# SmartCar_Arduino_V4.net
KiCad netlist of a schematic drawn in EAGLE
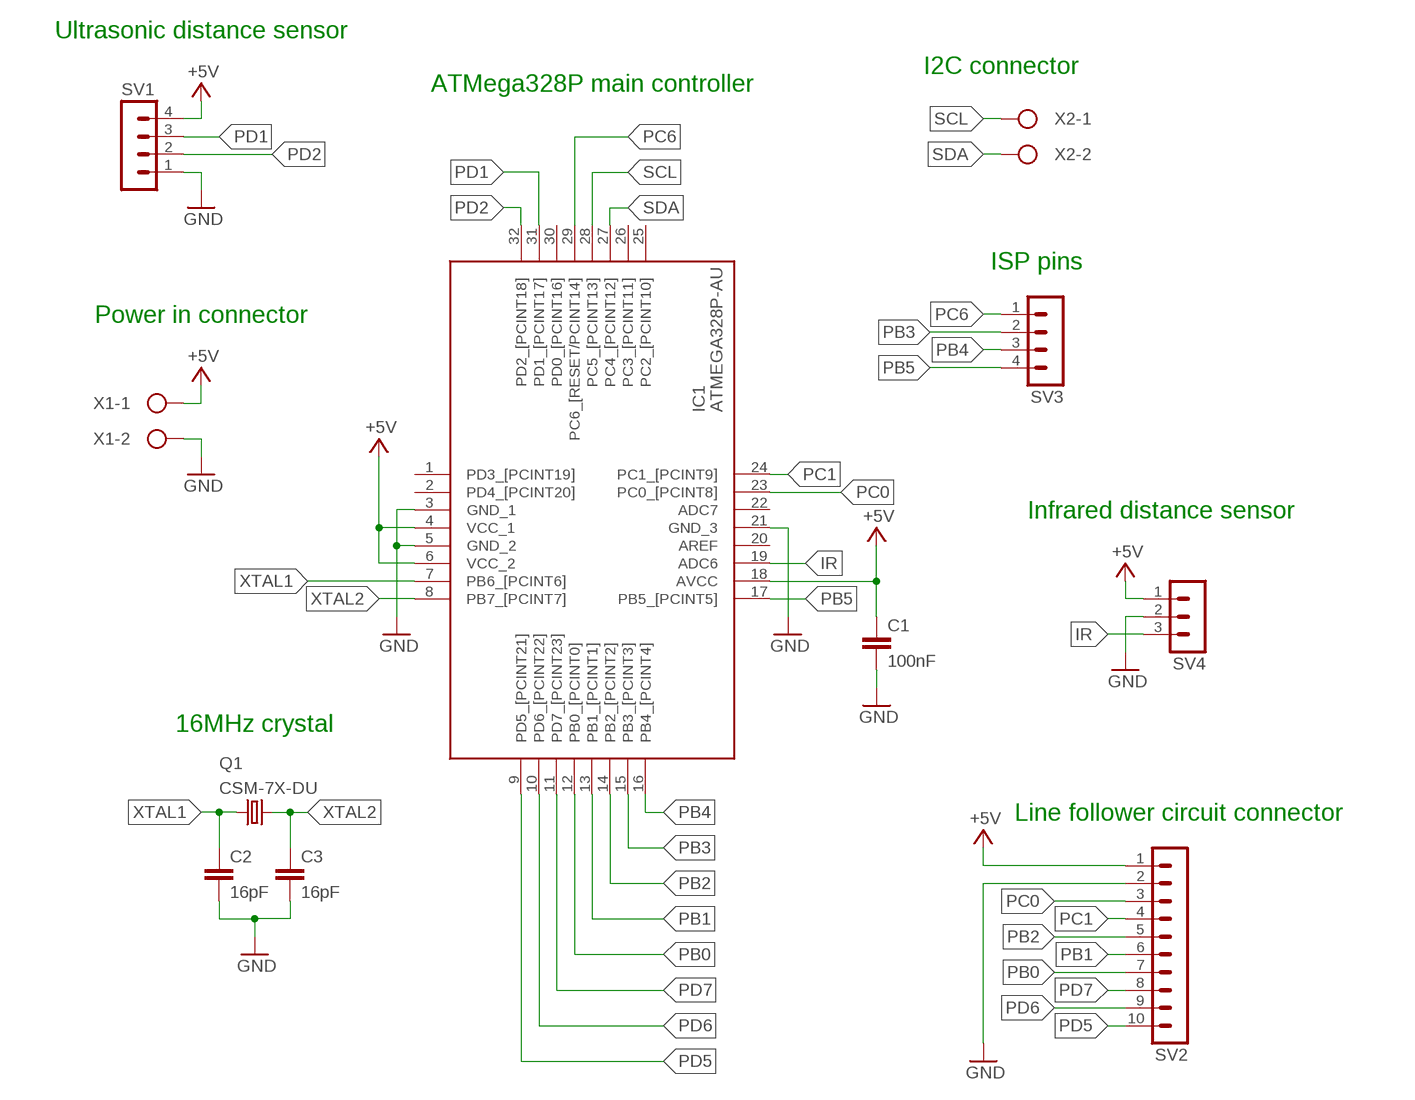
[diagram p0: schematic, sheet 1]

(export (version "E")
  (design (tool "Eeschema 10.0.6"))
  (components
    (comp (ref "C1")
      (value "100nF")
      (footprint "eagle-import:C0805")
      (libsource (lib "eagle-import") (part "C-EUC0805"))
    )
    (comp (ref "C2")
      (value "16pF")
      (footprint "eagle-import:C0805")
      (libsource (lib "eagle-import") (part "C-EUC0805"))
    )
    (comp (ref "C3")
      (value "16pF")
      (footprint "eagle-import:C0805")
      (libsource (lib "eagle-import") (part "C-EUC0805"))
    )
    (comp (ref "IC1")
      (value "ATMEGA328P-AU")
      (footprint "eagle-import:QFP80P900X900X120-32N")
      (fields (field (name "MOUSER_PART_NUMBER") "556-ATMEGA328P-AU"))
      (libsource (lib "eagle-import") (part "ATMEGA328P-AU"))
    )
    (comp (ref "Q1")
      (value "CSM-7X-DU")
      (footprint "eagle-import:CSM-7X-DU")
      (libsource (lib "eagle-import") (part "CSM-7X-DU"))
    )
    (comp (ref "SV1")
      (value "0")
      (footprint "eagle-import:MA04-1")
      (libsource (lib "eagle-import") (part "MA04-1"))
    )
    (comp (ref "SV2")
      (value "0")
      (footprint "eagle-import:MA10-1")
      (libsource (lib "eagle-import") (part "MA10-1"))
    )
    (comp (ref "SV3")
      (value "0")
      (footprint "eagle-import:MA04-1")
      (libsource (lib "eagle-import") (part "MA04-1"))
    )
    (comp (ref "SV4")
      (value "0")
      (footprint "eagle-import:MA03-1")
      (libsource (lib "eagle-import") (part "MA03-1"))
    )
    (comp (ref "X1")
      (value "0")
      (footprint "eagle-import:W237-102")
      (fields (field (name "MPN") "237-102"))
      (libsource (lib "eagle-import") (part "W237-102"))
    )
    (comp (ref "X2")
      (value "0")
      (footprint "eagle-import:W237-102")
      (fields (field (name "MPN") "237-102"))
      (libsource (lib "eagle-import") (part "W237-102"))
    )
  )
  (nets
    (net (code "1") (name "+5V") (class "Default")
      (node (ref "C1") (pin "1") (pinfunction "1_1") (pintype "passive"))
      (node (ref "IC1") (pin "18") (pinfunction "AVCC_18") (pintype "power_in"))
      (node (ref "IC1") (pin "4") (pinfunction "VCC_1_4") (pintype "power_in"))
      (node (ref "IC1") (pin "6") (pinfunction "VCC_2_6") (pintype "power_in"))
      (node (ref "SV1") (pin "4") (pinfunction "4_4") (pintype "passive"))
      (node (ref "SV2") (pin "1") (pinfunction "1_1") (pintype "passive"))
      (node (ref "SV4") (pin "1") (pinfunction "1_1") (pintype "passive"))
      (node (ref "X1") (pin "1") (pinfunction "KL_1") (pintype "passive"))
    )
    (net (code "2") (name "GND") (class "Default")
      (node (ref "C1") (pin "2") (pinfunction "2_2") (pintype "passive"))
      (node (ref "C2") (pin "2") (pinfunction "2_2") (pintype "passive"))
      (node (ref "C3") (pin "2") (pinfunction "2_2") (pintype "passive"))
      (node (ref "IC1") (pin "21") (pinfunction "GND_3_21") (pintype "power_in"))
      (node (ref "IC1") (pin "3") (pinfunction "GND_1_3") (pintype "power_in"))
      (node (ref "IC1") (pin "5") (pinfunction "GND_2_5") (pintype "power_in"))
      (node (ref "SV1") (pin "1") (pinfunction "1_1") (pintype "passive"))
      (node (ref "SV2") (pin "2") (pinfunction "2_2") (pintype "passive"))
      (node (ref "SV4") (pin "2") (pinfunction "2_2") (pintype "passive"))
      (node (ref "X1") (pin "2") (pinfunction "KL_2") (pintype "passive"))
    )
    (net (code "3") (name "IR") (class "Default")
      (node (ref "IC1") (pin "19") (pinfunction "ADC6_19") (pintype "bidirectional"))
      (node (ref "SV4") (pin "3") (pinfunction "3_3") (pintype "passive"))
    )
    (net (code "4") (name "PB0") (class "Default")
      (node (ref "IC1") (pin "12") (pinfunction "PB0_[PCINT0]_12") (pintype "bidirectional"))
      (node (ref "SV2") (pin "7") (pinfunction "7_7") (pintype "passive"))
    )
    (net (code "5") (name "PB1") (class "Default")
      (node (ref "IC1") (pin "13") (pinfunction "PB1_[PCINT1]_13") (pintype "bidirectional"))
      (node (ref "SV2") (pin "6") (pinfunction "6_6") (pintype "passive"))
    )
    (net (code "6") (name "PB2") (class "Default")
      (node (ref "IC1") (pin "14") (pinfunction "PB2_[PCINT2]_14") (pintype "bidirectional"))
      (node (ref "SV2") (pin "5") (pinfunction "5_5") (pintype "passive"))
    )
    (net (code "7") (name "PB3") (class "Default")
      (node (ref "IC1") (pin "15") (pinfunction "PB3_[PCINT3]_15") (pintype "bidirectional"))
      (node (ref "SV3") (pin "2") (pinfunction "2_2") (pintype "passive"))
    )
    (net (code "8") (name "PB4") (class "Default")
      (node (ref "IC1") (pin "16") (pinfunction "PB4_[PCINT4]_16") (pintype "bidirectional"))
      (node (ref "SV3") (pin "3") (pinfunction "3_3") (pintype "passive"))
    )
    (net (code "9") (name "PB5") (class "Default")
      (node (ref "IC1") (pin "17") (pinfunction "PB5_[PCINT5]_17") (pintype "bidirectional"))
      (node (ref "SV3") (pin "4") (pinfunction "4_4") (pintype "passive"))
    )
    (net (code "10") (name "PC0") (class "Default")
      (node (ref "IC1") (pin "23") (pinfunction "PC0_[PCINT8]_23") (pintype "bidirectional"))
      (node (ref "SV2") (pin "3") (pinfunction "3_3") (pintype "passive"))
    )
    (net (code "11") (name "PC1") (class "Default")
      (node (ref "IC1") (pin "24") (pinfunction "PC1_[PCINT9]_24") (pintype "bidirectional"))
      (node (ref "SV2") (pin "4") (pinfunction "4_4") (pintype "passive"))
    )
    (net (code "12") (name "PC6") (class "Default")
      (node (ref "IC1") (pin "29") (pinfunction "PC6_[RESET/PCINT14]_29") (pintype "bidirectional"))
      (node (ref "SV3") (pin "1") (pinfunction "1_1") (pintype "passive"))
    )
    (net (code "13") (name "PD1") (class "Default")
      (node (ref "IC1") (pin "31") (pinfunction "PD1_[PCINT17]_31") (pintype "bidirectional"))
      (node (ref "SV1") (pin "3") (pinfunction "3_3") (pintype "passive"))
    )
    (net (code "14") (name "PD2") (class "Default")
      (node (ref "IC1") (pin "32") (pinfunction "PD2_[PCINT18]_32") (pintype "bidirectional"))
      (node (ref "SV1") (pin "2") (pinfunction "2_2") (pintype "passive"))
    )
    (net (code "15") (name "PD5") (class "Default")
      (node (ref "IC1") (pin "9") (pinfunction "PD5_[PCINT21]_9") (pintype "bidirectional"))
      (node (ref "SV2") (pin "10") (pinfunction "10_10") (pintype "passive"))
    )
    (net (code "16") (name "PD6") (class "Default")
      (node (ref "IC1") (pin "10") (pinfunction "PD6_[PCINT22]_10") (pintype "bidirectional"))
      (node (ref "SV2") (pin "9") (pinfunction "9_9") (pintype "passive"))
    )
    (net (code "17") (name "PD7") (class "Default")
      (node (ref "IC1") (pin "11") (pinfunction "PD7_[PCINT23]_11") (pintype "bidirectional"))
      (node (ref "SV2") (pin "8") (pinfunction "8_8") (pintype "passive"))
    )
    (net (code "18") (name "SCL") (class "Default")
      (node (ref "IC1") (pin "28") (pinfunction "PC5_[PCINT13]_28") (pintype "bidirectional"))
      (node (ref "X2") (pin "1") (pinfunction "KL_1") (pintype "passive"))
    )
    (net (code "19") (name "SDA") (class "Default")
      (node (ref "IC1") (pin "27") (pinfunction "PC4_[PCINT12]_27") (pintype "bidirectional"))
      (node (ref "X2") (pin "2") (pinfunction "KL_2") (pintype "passive"))
    )
    (net (code "20") (name "XTAL1") (class "Default")
      (node (ref "C2") (pin "1") (pinfunction "1_1") (pintype "passive"))
      (node (ref "IC1") (pin "7") (pinfunction "PB6_[PCINT6]_7") (pintype "bidirectional"))
      (node (ref "Q1") (pin "1") (pinfunction "1_1") (pintype "passive"))
    )
    (net (code "21") (name "XTAL2") (class "Default")
      (node (ref "C3") (pin "1") (pinfunction "1_1") (pintype "passive"))
      (node (ref "IC1") (pin "8") (pinfunction "PB7_[PCINT7]_8") (pintype "bidirectional"))
      (node (ref "Q1") (pin "2") (pinfunction "2_2") (pintype "passive"))
    )
    (net (code "22") (name "unconnected-(IC1-ADC7-Pad22)") (class "Default")
      (node (ref "IC1") (pin "22") (pinfunction "ADC7_22") (pintype "bidirectional"))
    )
    (net (code "23") (name "unconnected-(IC1-AREF-Pad20)") (class "Default")
      (node (ref "IC1") (pin "20") (pinfunction "AREF_20") (pintype "bidirectional"))
    )
    (net (code "24") (name "unconnected-(IC1-PC2_[PCINT10]-Pad25)") (class "Default")
      (node (ref "IC1") (pin "25") (pinfunction "PC2_[PCINT10]_25") (pintype "bidirectional"))
    )
    (net (code "25") (name "unconnected-(IC1-PC3_[PCINT11]-Pad26)") (class "Default")
      (node (ref "IC1") (pin "26") (pinfunction "PC3_[PCINT11]_26") (pintype "bidirectional"))
    )
    (net (code "26") (name "unconnected-(IC1-PD0_[PCINT16]-Pad30)") (class "Default")
      (node (ref "IC1") (pin "30") (pinfunction "PD0_[PCINT16]_30") (pintype "bidirectional"))
    )
    (net (code "27") (name "unconnected-(IC1-PD3_[PCINT19]-Pad1)") (class "Default")
      (node (ref "IC1") (pin "1") (pinfunction "PD3_[PCINT19]_1") (pintype "bidirectional"))
    )
    (net (code "28") (name "unconnected-(IC1-PD4_[PCINT20]-Pad2)") (class "Default")
      (node (ref "IC1") (pin "2") (pinfunction "PD4_[PCINT20]_2") (pintype "bidirectional"))
    )
  )
)
